# moodLighting.net
KiCad netlist of a schematic drawn in EAGLE
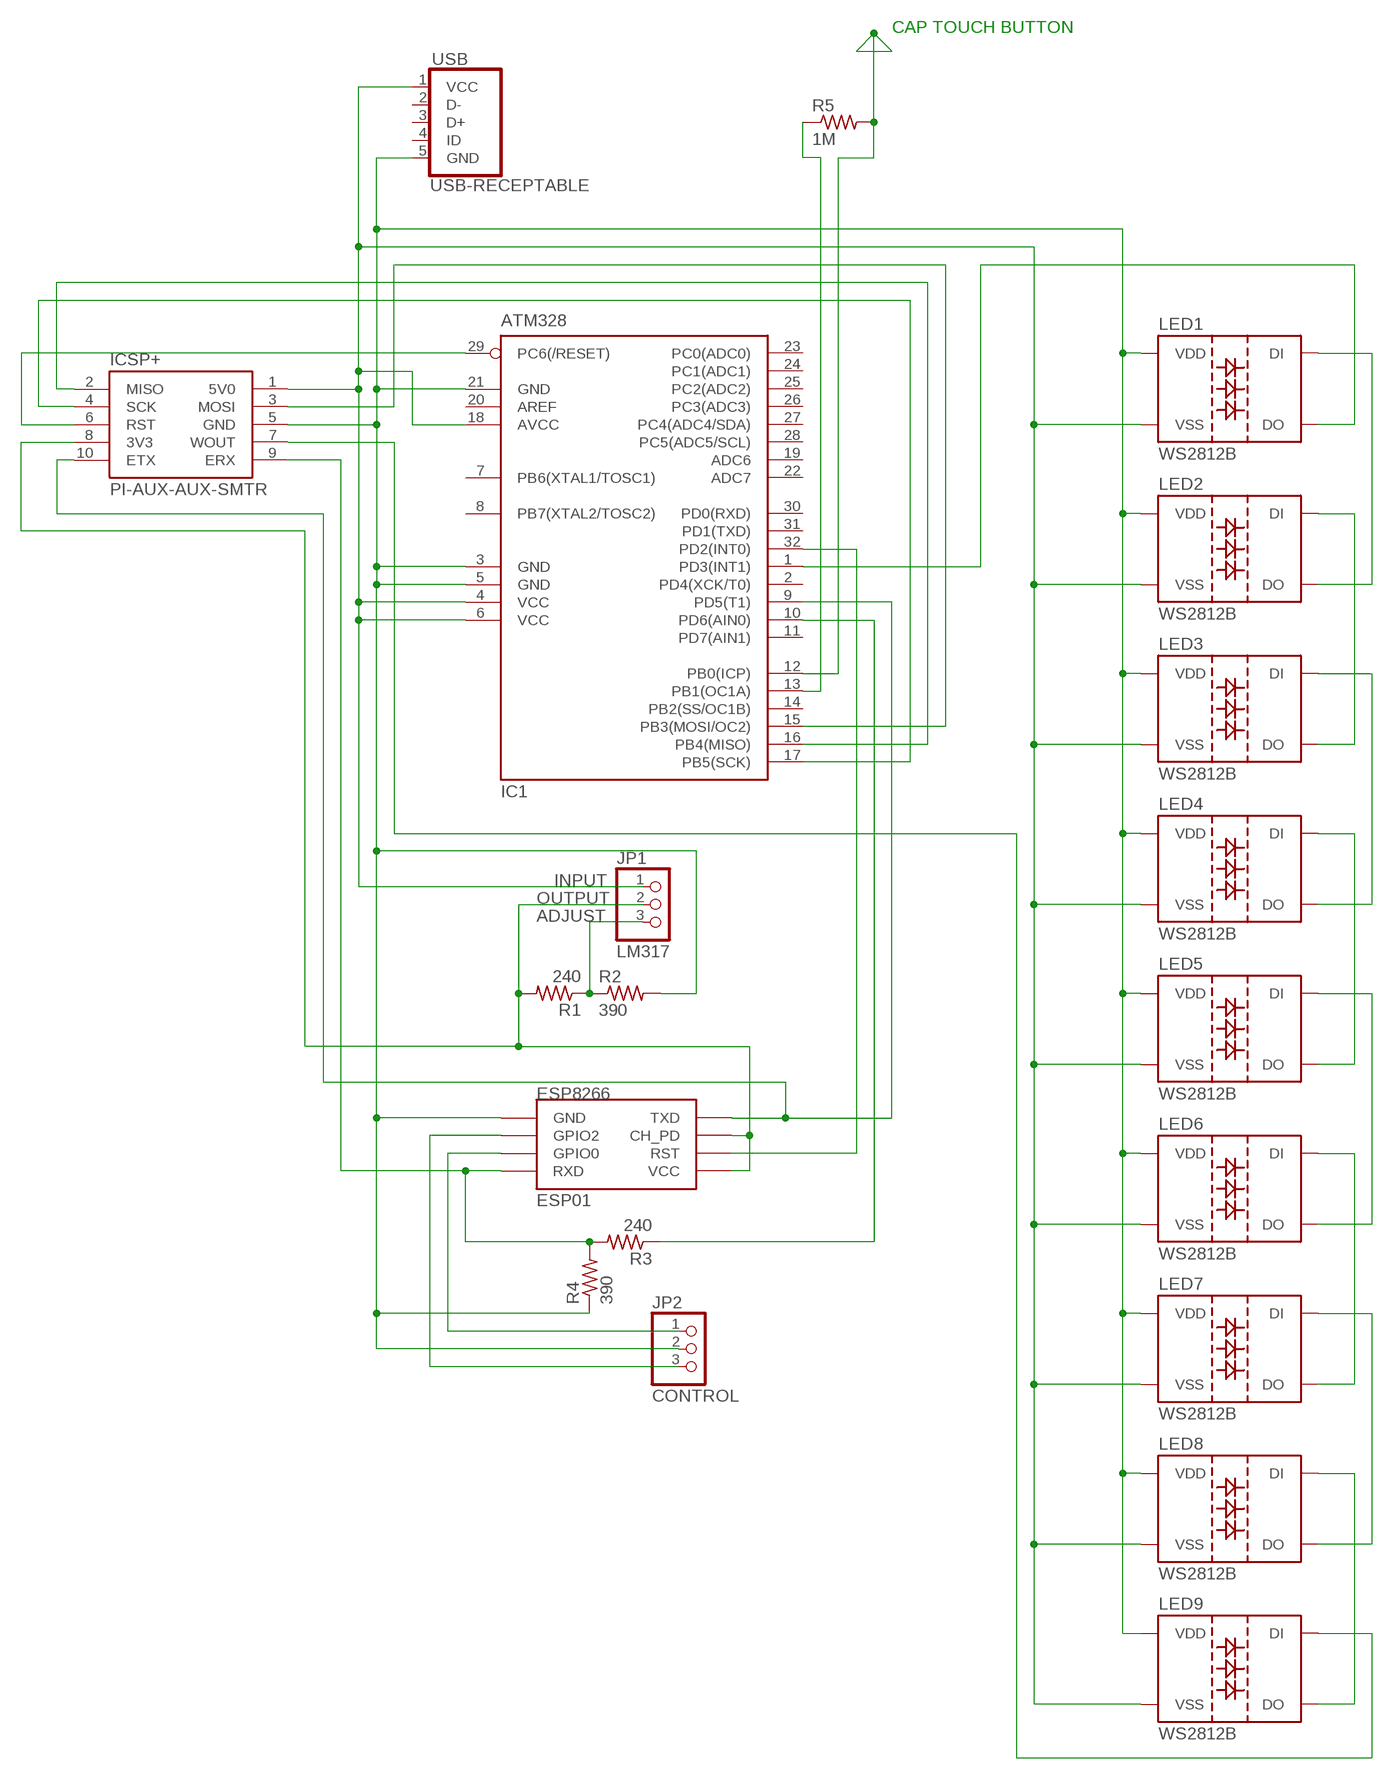
[diagram p0: schematic, sheet 1]

(export (version "E")
  (design (tool "Eeschema 10.0.6"))
  (components
    (comp (ref "ESP8266")
      (value "ESP01")
      (footprint "eagle-import:ESP01")
      (libsource (lib "eagle-import") (part "ESP01"))
    )
    (comp (ref "IC1")
      (value "ATM328")
      (footprint "eagle-import:TQFP32-08")
      (fields (field (name "MPN") "ATMEGA8-16AU"))
      (libsource (lib "eagle-import") (part "MEGA8-AI"))
    )
    (comp (ref "ICSP+")
      (value "PI-AUX-AUX-SMTR")
      (footprint "eagle-import:GPIO-AUX-CONNECTOR-SMT-REV")
      (libsource (lib "eagle-import") (part "PI-AUX-AUX-SMTR"))
    )
    (comp (ref "JP1")
      (value "LM317")
      (footprint "eagle-import:1X03")
      (libsource (lib "eagle-import") (part "PINHD-1X3"))
    )
    (comp (ref "JP2")
      (value "CONTROL")
      (footprint "eagle-import:1X03")
      (libsource (lib "eagle-import") (part "PINHD-1X3"))
    )
    (comp (ref "LED1")
      (value "WS2812B")
      (footprint "eagle-import:WS2812B")
      (libsource (lib "eagle-import") (part "WS2812B"))
    )
    (comp (ref "LED2")
      (value "WS2812B")
      (footprint "eagle-import:WS2812B")
      (libsource (lib "eagle-import") (part "WS2812B"))
    )
    (comp (ref "LED3")
      (value "WS2812B")
      (footprint "eagle-import:WS2812B")
      (libsource (lib "eagle-import") (part "WS2812B"))
    )
    (comp (ref "LED4")
      (value "WS2812B")
      (footprint "eagle-import:WS2812B")
      (libsource (lib "eagle-import") (part "WS2812B"))
    )
    (comp (ref "LED5")
      (value "WS2812B")
      (footprint "eagle-import:WS2812B")
      (libsource (lib "eagle-import") (part "WS2812B"))
    )
    (comp (ref "LED6")
      (value "WS2812B")
      (footprint "eagle-import:WS2812B")
      (libsource (lib "eagle-import") (part "WS2812B"))
    )
    (comp (ref "LED7")
      (value "WS2812B")
      (footprint "eagle-import:WS2812B")
      (libsource (lib "eagle-import") (part "WS2812B"))
    )
    (comp (ref "LED8")
      (value "WS2812B")
      (footprint "eagle-import:WS2812B")
      (libsource (lib "eagle-import") (part "WS2812B"))
    )
    (comp (ref "LED9")
      (value "WS2812B")
      (footprint "eagle-import:WS2812B")
      (libsource (lib "eagle-import") (part "WS2812B"))
    )
    (comp (ref "R1")
      (value "240")
      (footprint "eagle-import:R0805")
      (libsource (lib "eagle-import") (part "R-US_R0805"))
    )
    (comp (ref "R2")
      (value "390")
      (footprint "eagle-import:R0805")
      (libsource (lib "eagle-import") (part "R-US_R0805"))
    )
    (comp (ref "R3")
      (value "240")
      (footprint "eagle-import:R0805")
      (libsource (lib "eagle-import") (part "R-US_R0805"))
    )
    (comp (ref "R4")
      (value "390")
      (footprint "eagle-import:R0805")
      (libsource (lib "eagle-import") (part "R-US_R0805"))
    )
    (comp (ref "R5")
      (value "1M")
      (footprint "eagle-import:R0805")
      (libsource (lib "eagle-import") (part "R-US_R0805"))
    )
    (comp (ref "USB")
      (value "USB-RECEPTABLE")
      (footprint "eagle-import:FCI-10103594-0001LF")
      (libsource (lib "eagle-import") (part "USB-RECEPTABLE"))
    )
  )
  (nets
    (net (code "1") (name "Net-(ESP8266-PadGPIO0)") (class "Default")
      (node (ref "ESP8266") (pin "GPIO0") (pinfunction "GPIO0_GPIO0") (pintype "bidirectional"))
      (node (ref "JP2") (pin "1") (pinfunction "1_1") (pintype "passive"))
    )
    (net (code "2") (name "Net-(ESP8266-PadGPIO2)") (class "Default")
      (node (ref "ESP8266") (pin "GPIO2") (pinfunction "GPIO2_GPIO2") (pintype "bidirectional"))
      (node (ref "JP2") (pin "3") (pinfunction "3_3") (pintype "passive"))
    )
    (net (code "3") (name "Net-(ESP8266-RXD)") (class "Default")
      (node (ref "ESP8266") (pin "RX") (pinfunction "RXD_RX") (pintype "bidirectional"))
      (node (ref "ICSP+") (pin "9") (pinfunction "ERX_9") (pintype "bidirectional"))
      (node (ref "R3") (pin "2") (pinfunction "2_2") (pintype "passive"))
      (node (ref "R4") (pin "2") (pinfunction "2_2") (pintype "passive"))
    )
    (net (code "4") (name "Net-(ESP8266-TXD)") (class "Default")
      (node (ref "ESP8266") (pin "TX") (pinfunction "TXD_TX") (pintype "bidirectional"))
      (node (ref "IC1") (pin "9") (pinfunction "PD5(T1)_9") (pintype "bidirectional"))
      (node (ref "ICSP+") (pin "10") (pinfunction "ETX_10") (pintype "bidirectional"))
    )
    (net (code "5") (name "Net-(IC1-AVCC)") (class "Default")
      (node (ref "IC1") (pin "18") (pinfunction "AVCC_18") (pintype "power_in"))
      (node (ref "IC1") (pin "4") (pinfunction "VCC_4") (pintype "power_in"))
      (node (ref "IC1") (pin "6") (pinfunction "VCC_6") (pintype "power_in"))
      (node (ref "ICSP+") (pin "1") (pinfunction "5V0_1") (pintype "power_in"))
      (node (ref "JP1") (pin "1") (pinfunction "1_1") (pintype "passive"))
      (node (ref "LED1") (pin "3") (pinfunction "VSS_3") (pintype "bidirectional"))
      (node (ref "LED2") (pin "3") (pinfunction "VSS_3") (pintype "bidirectional"))
      (node (ref "LED3") (pin "3") (pinfunction "VSS_3") (pintype "bidirectional"))
      (node (ref "LED4") (pin "3") (pinfunction "VSS_3") (pintype "bidirectional"))
      (node (ref "LED5") (pin "3") (pinfunction "VSS_3") (pintype "bidirectional"))
      (node (ref "LED6") (pin "3") (pinfunction "VSS_3") (pintype "bidirectional"))
      (node (ref "LED7") (pin "3") (pinfunction "VSS_3") (pintype "bidirectional"))
      (node (ref "LED8") (pin "3") (pinfunction "VSS_3") (pintype "bidirectional"))
      (node (ref "LED9") (pin "3") (pinfunction "VSS_3") (pintype "bidirectional"))
      (node (ref "USB") (pin "1") (pinfunction "VCC_1") (pintype "bidirectional"))
    )
    (net (code "6") (name "Net-(IC1-PB0(ICP))") (class "Default")
      (node (ref "IC1") (pin "12") (pinfunction "PB0(ICP)_12") (pintype "bidirectional"))
      (node (ref "R5") (pin "2") (pinfunction "2_2") (pintype "passive"))
    )
    (net (code "7") (name "Net-(IC1-PB1(OC1A))") (class "Default")
      (node (ref "IC1") (pin "13") (pinfunction "PB1(OC1A)_13") (pintype "bidirectional"))
      (node (ref "R5") (pin "1") (pinfunction "1_1") (pintype "passive"))
    )
    (net (code "8") (name "Net-(IC1-PB3(MOSI{slash}OC2))") (class "Default")
      (node (ref "IC1") (pin "15") (pinfunction "PB3(MOSI/OC2)_15") (pintype "bidirectional"))
      (node (ref "ICSP+") (pin "3") (pinfunction "MOSI_3") (pintype "bidirectional"))
    )
    (net (code "9") (name "Net-(IC1-PB4(MISO))") (class "Default")
      (node (ref "IC1") (pin "16") (pinfunction "PB4(MISO)_16") (pintype "bidirectional"))
      (node (ref "ICSP+") (pin "2") (pinfunction "MISO_2") (pintype "bidirectional"))
    )
    (net (code "10") (name "Net-(IC1-PB5(SCK))") (class "Default")
      (node (ref "IC1") (pin "17") (pinfunction "PB5(SCK)_17") (pintype "bidirectional"))
      (node (ref "ICSP+") (pin "4") (pinfunction "SCK_4") (pintype "bidirectional"))
    )
    (net (code "11") (name "Net-(IC1-PC6({slash}RESET))") (class "Default")
      (node (ref "IC1") (pin "29") (pinfunction "PC6(/RESET)_29") (pintype "bidirectional"))
      (node (ref "ICSP+") (pin "6") (pinfunction "RST_6") (pintype "bidirectional"))
    )
    (net (code "12") (name "Net-(IC1-PD2(INT0))") (class "Default")
      (node (ref "ESP8266") (pin "RST") (pinfunction "RST_RST") (pintype "bidirectional"))
      (node (ref "IC1") (pin "32") (pinfunction "PD2(INT0)_32") (pintype "bidirectional"))
    )
    (net (code "13") (name "Net-(IC1-PD3(INT1))") (class "Default")
      (node (ref "IC1") (pin "1") (pinfunction "PD3(INT1)_1") (pintype "bidirectional"))
      (node (ref "LED1") (pin "2") (pinfunction "DO_2") (pintype "bidirectional"))
    )
    (net (code "14") (name "Net-(IC1-PD6(AIN0))") (class "Default")
      (node (ref "IC1") (pin "10") (pinfunction "PD6(AIN0)_10") (pintype "bidirectional"))
      (node (ref "R3") (pin "1") (pinfunction "1_1") (pintype "passive"))
    )
    (net (code "15") (name "Net-(ICSP+-3V3)") (class "Default")
      (node (ref "ESP8266") (pin "CH_PD") (pinfunction "CH_PD_CH_PD") (pintype "bidirectional"))
      (node (ref "ESP8266") (pin "VCC") (pinfunction "VCC_VCC") (pintype "bidirectional"))
      (node (ref "ICSP+") (pin "8") (pinfunction "3V3_8") (pintype "power_in"))
      (node (ref "JP1") (pin "2") (pinfunction "2_2") (pintype "passive"))
      (node (ref "R1") (pin "2") (pinfunction "2_2") (pintype "passive"))
    )
    (net (code "16") (name "Net-(ICSP+-GND)") (class "Default")
      (node (ref "ESP8266") (pin "GND") (pinfunction "GND_GND") (pintype "bidirectional"))
      (node (ref "IC1") (pin "21") (pinfunction "GND_21") (pintype "power_in"))
      (node (ref "IC1") (pin "3") (pinfunction "GND_3") (pintype "power_in"))
      (node (ref "IC1") (pin "5") (pinfunction "GND_5") (pintype "power_in"))
      (node (ref "ICSP+") (pin "5") (pinfunction "GND_5") (pintype "power_in"))
      (node (ref "JP2") (pin "2") (pinfunction "2_2") (pintype "passive"))
      (node (ref "LED1") (pin "1") (pinfunction "VDD_1") (pintype "bidirectional"))
      (node (ref "LED2") (pin "1") (pinfunction "VDD_1") (pintype "bidirectional"))
      (node (ref "LED3") (pin "1") (pinfunction "VDD_1") (pintype "bidirectional"))
      (node (ref "LED4") (pin "1") (pinfunction "VDD_1") (pintype "bidirectional"))
      (node (ref "LED5") (pin "1") (pinfunction "VDD_1") (pintype "bidirectional"))
      (node (ref "LED6") (pin "1") (pinfunction "VDD_1") (pintype "bidirectional"))
      (node (ref "LED7") (pin "1") (pinfunction "VDD_1") (pintype "bidirectional"))
      (node (ref "LED8") (pin "1") (pinfunction "VDD_1") (pintype "bidirectional"))
      (node (ref "LED9") (pin "1") (pinfunction "VDD_1") (pintype "bidirectional"))
      (node (ref "R2") (pin "2") (pinfunction "2_2") (pintype "passive"))
      (node (ref "R4") (pin "1") (pinfunction "1_1") (pintype "passive"))
      (node (ref "USB") (pin "5") (pinfunction "GND_5") (pintype "bidirectional"))
    )
    (net (code "17") (name "Net-(ICSP+-WOUT)") (class "Default")
      (node (ref "ICSP+") (pin "7") (pinfunction "WOUT_7") (pintype "bidirectional"))
      (node (ref "LED9") (pin "4") (pinfunction "DI_4") (pintype "bidirectional"))
    )
    (net (code "18") (name "Net-(JP1-Pad3)") (class "Default")
      (node (ref "JP1") (pin "3") (pinfunction "3_3") (pintype "passive"))
      (node (ref "R1") (pin "1") (pinfunction "1_1") (pintype "passive"))
      (node (ref "R2") (pin "1") (pinfunction "1_1") (pintype "passive"))
    )
    (net (code "19") (name "Net-(LED1-DI)") (class "Default")
      (node (ref "LED1") (pin "4") (pinfunction "DI_4") (pintype "bidirectional"))
      (node (ref "LED2") (pin "2") (pinfunction "DO_2") (pintype "bidirectional"))
    )
    (net (code "20") (name "Net-(LED2-DI)") (class "Default")
      (node (ref "LED2") (pin "4") (pinfunction "DI_4") (pintype "bidirectional"))
      (node (ref "LED3") (pin "2") (pinfunction "DO_2") (pintype "bidirectional"))
    )
    (net (code "21") (name "Net-(LED3-DI)") (class "Default")
      (node (ref "LED3") (pin "4") (pinfunction "DI_4") (pintype "bidirectional"))
      (node (ref "LED4") (pin "2") (pinfunction "DO_2") (pintype "bidirectional"))
    )
    (net (code "22") (name "Net-(LED4-DI)") (class "Default")
      (node (ref "LED4") (pin "4") (pinfunction "DI_4") (pintype "bidirectional"))
      (node (ref "LED5") (pin "2") (pinfunction "DO_2") (pintype "bidirectional"))
    )
    (net (code "23") (name "Net-(LED5-DI)") (class "Default")
      (node (ref "LED5") (pin "4") (pinfunction "DI_4") (pintype "bidirectional"))
      (node (ref "LED6") (pin "2") (pinfunction "DO_2") (pintype "bidirectional"))
    )
    (net (code "24") (name "Net-(LED6-DI)") (class "Default")
      (node (ref "LED6") (pin "4") (pinfunction "DI_4") (pintype "bidirectional"))
      (node (ref "LED7") (pin "2") (pinfunction "DO_2") (pintype "bidirectional"))
    )
    (net (code "25") (name "Net-(LED7-DI)") (class "Default")
      (node (ref "LED7") (pin "4") (pinfunction "DI_4") (pintype "bidirectional"))
      (node (ref "LED8") (pin "2") (pinfunction "DO_2") (pintype "bidirectional"))
    )
    (net (code "26") (name "Net-(LED8-DI)") (class "Default")
      (node (ref "LED8") (pin "4") (pinfunction "DI_4") (pintype "bidirectional"))
      (node (ref "LED9") (pin "2") (pinfunction "DO_2") (pintype "bidirectional"))
    )
    (net (code "27") (name "unconnected-(IC1-ADC6-Pad19)") (class "Default")
      (node (ref "IC1") (pin "19") (pinfunction "ADC6_19") (pintype "bidirectional"))
    )
    (net (code "28") (name "unconnected-(IC1-ADC7-Pad22)") (class "Default")
      (node (ref "IC1") (pin "22") (pinfunction "ADC7_22") (pintype "bidirectional"))
    )
    (net (code "29") (name "unconnected-(IC1-AREF-Pad20)") (class "Default")
      (node (ref "IC1") (pin "20") (pinfunction "AREF_20") (pintype "passive"))
    )
    (net (code "30") (name "unconnected-(IC1-PB2(SS{slash}OC1B)-Pad14)") (class "Default")
      (node (ref "IC1") (pin "14") (pinfunction "PB2(SS/OC1B)_14") (pintype "bidirectional"))
    )
    (net (code "31") (name "unconnected-(IC1-PB6(XTAL1{slash}TOSC1)-Pad7)") (class "Default")
      (node (ref "IC1") (pin "7") (pinfunction "PB6(XTAL1/TOSC1)_7") (pintype "bidirectional"))
    )
    (net (code "32") (name "unconnected-(IC1-PB7(XTAL2{slash}TOSC2)-Pad8)") (class "Default")
      (node (ref "IC1") (pin "8") (pinfunction "PB7(XTAL2/TOSC2)_8") (pintype "bidirectional"))
    )
    (net (code "33") (name "unconnected-(IC1-PC0(ADC0)-Pad23)") (class "Default")
      (node (ref "IC1") (pin "23") (pinfunction "PC0(ADC0)_23") (pintype "bidirectional"))
    )
    (net (code "34") (name "unconnected-(IC1-PC1(ADC1)-Pad24)") (class "Default")
      (node (ref "IC1") (pin "24") (pinfunction "PC1(ADC1)_24") (pintype "bidirectional"))
    )
    (net (code "35") (name "unconnected-(IC1-PC2(ADC2)-Pad25)") (class "Default")
      (node (ref "IC1") (pin "25") (pinfunction "PC2(ADC2)_25") (pintype "bidirectional"))
    )
    (net (code "36") (name "unconnected-(IC1-PC3(ADC3)-Pad26)") (class "Default")
      (node (ref "IC1") (pin "26") (pinfunction "PC3(ADC3)_26") (pintype "bidirectional"))
    )
    (net (code "37") (name "unconnected-(IC1-PC4(ADC4{slash}SDA)-Pad27)") (class "Default")
      (node (ref "IC1") (pin "27") (pinfunction "PC4(ADC4/SDA)_27") (pintype "bidirectional"))
    )
    (net (code "38") (name "unconnected-(IC1-PC5(ADC5{slash}SCL)-Pad28)") (class "Default")
      (node (ref "IC1") (pin "28") (pinfunction "PC5(ADC5/SCL)_28") (pintype "bidirectional"))
    )
    (net (code "39") (name "unconnected-(IC1-PD0(RXD)-Pad30)") (class "Default")
      (node (ref "IC1") (pin "30") (pinfunction "PD0(RXD)_30") (pintype "bidirectional"))
    )
    (net (code "40") (name "unconnected-(IC1-PD1(TXD)-Pad31)") (class "Default")
      (node (ref "IC1") (pin "31") (pinfunction "PD1(TXD)_31") (pintype "bidirectional"))
    )
    (net (code "41") (name "unconnected-(IC1-PD4(XCK{slash}T0)-Pad2)") (class "Default")
      (node (ref "IC1") (pin "2") (pinfunction "PD4(XCK/T0)_2") (pintype "bidirectional"))
    )
    (net (code "42") (name "unconnected-(IC1-PD7(AIN1)-Pad11)") (class "Default")
      (node (ref "IC1") (pin "11") (pinfunction "PD7(AIN1)_11") (pintype "bidirectional"))
    )
    (net (code "43") (name "unconnected-(USB-D+-Pad3)") (class "Default")
      (node (ref "USB") (pin "3") (pinfunction "D+_3") (pintype "bidirectional"))
    )
    (net (code "44") (name "unconnected-(USB-D--Pad2)") (class "Default")
      (node (ref "USB") (pin "2") (pinfunction "D-_2") (pintype "bidirectional"))
    )
    (net (code "45") (name "unconnected-(USB-ID-Pad4)") (class "Default")
      (node (ref "USB") (pin "4") (pinfunction "ID_4") (pintype "bidirectional"))
    )
  )
)
